# HGD_Sensor_v0_1_-20200729.net
KiCad netlist of a schematic drawn in Altium Designer
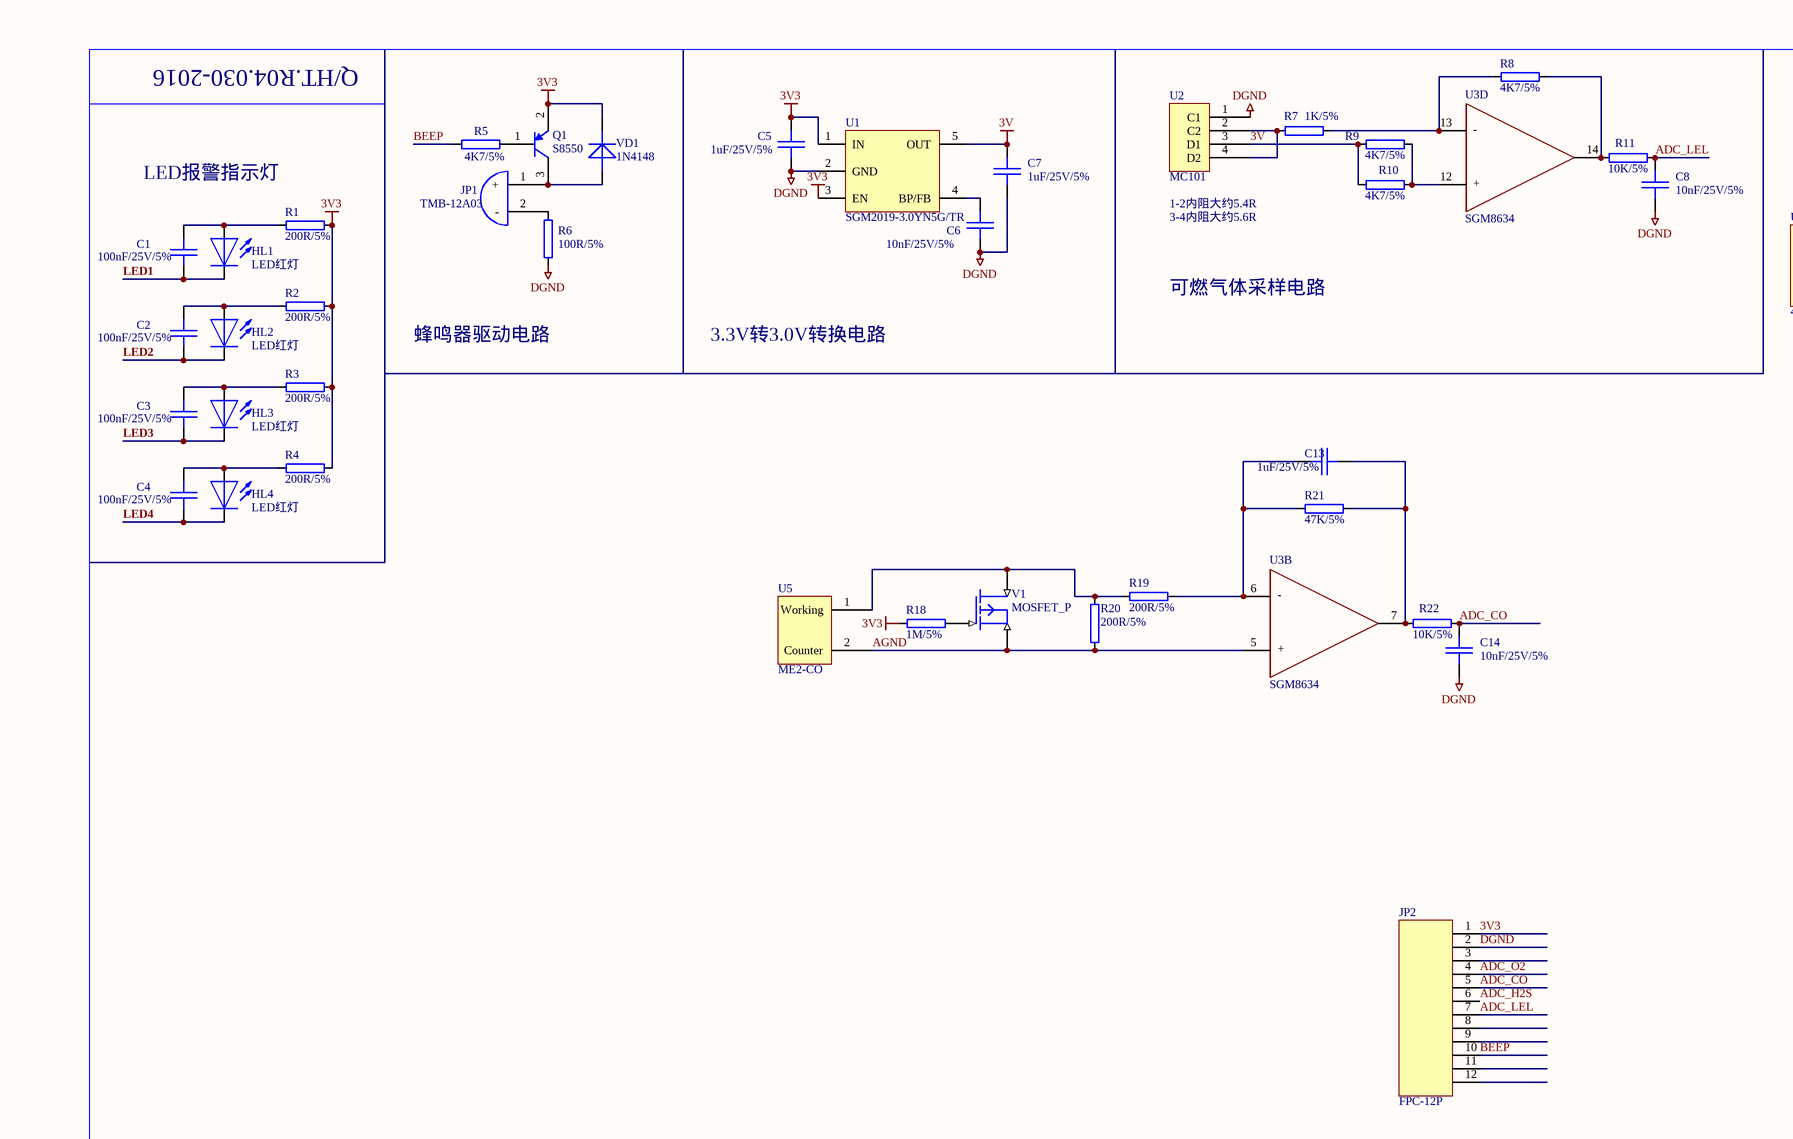
[diagram p0: HGD_Sensor(v0.1)-20200729.SchDoc, top left]
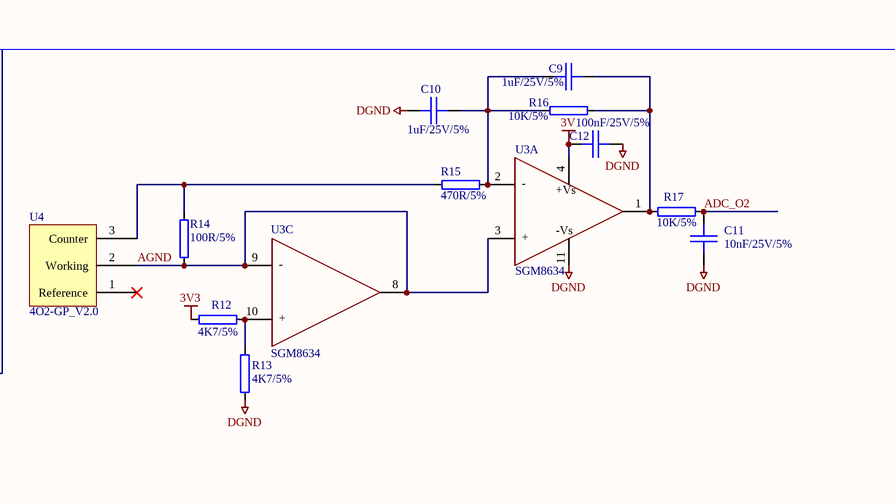
[diagram p1: HGD_Sensor(v0.1)-20200729.SchDoc, top right]
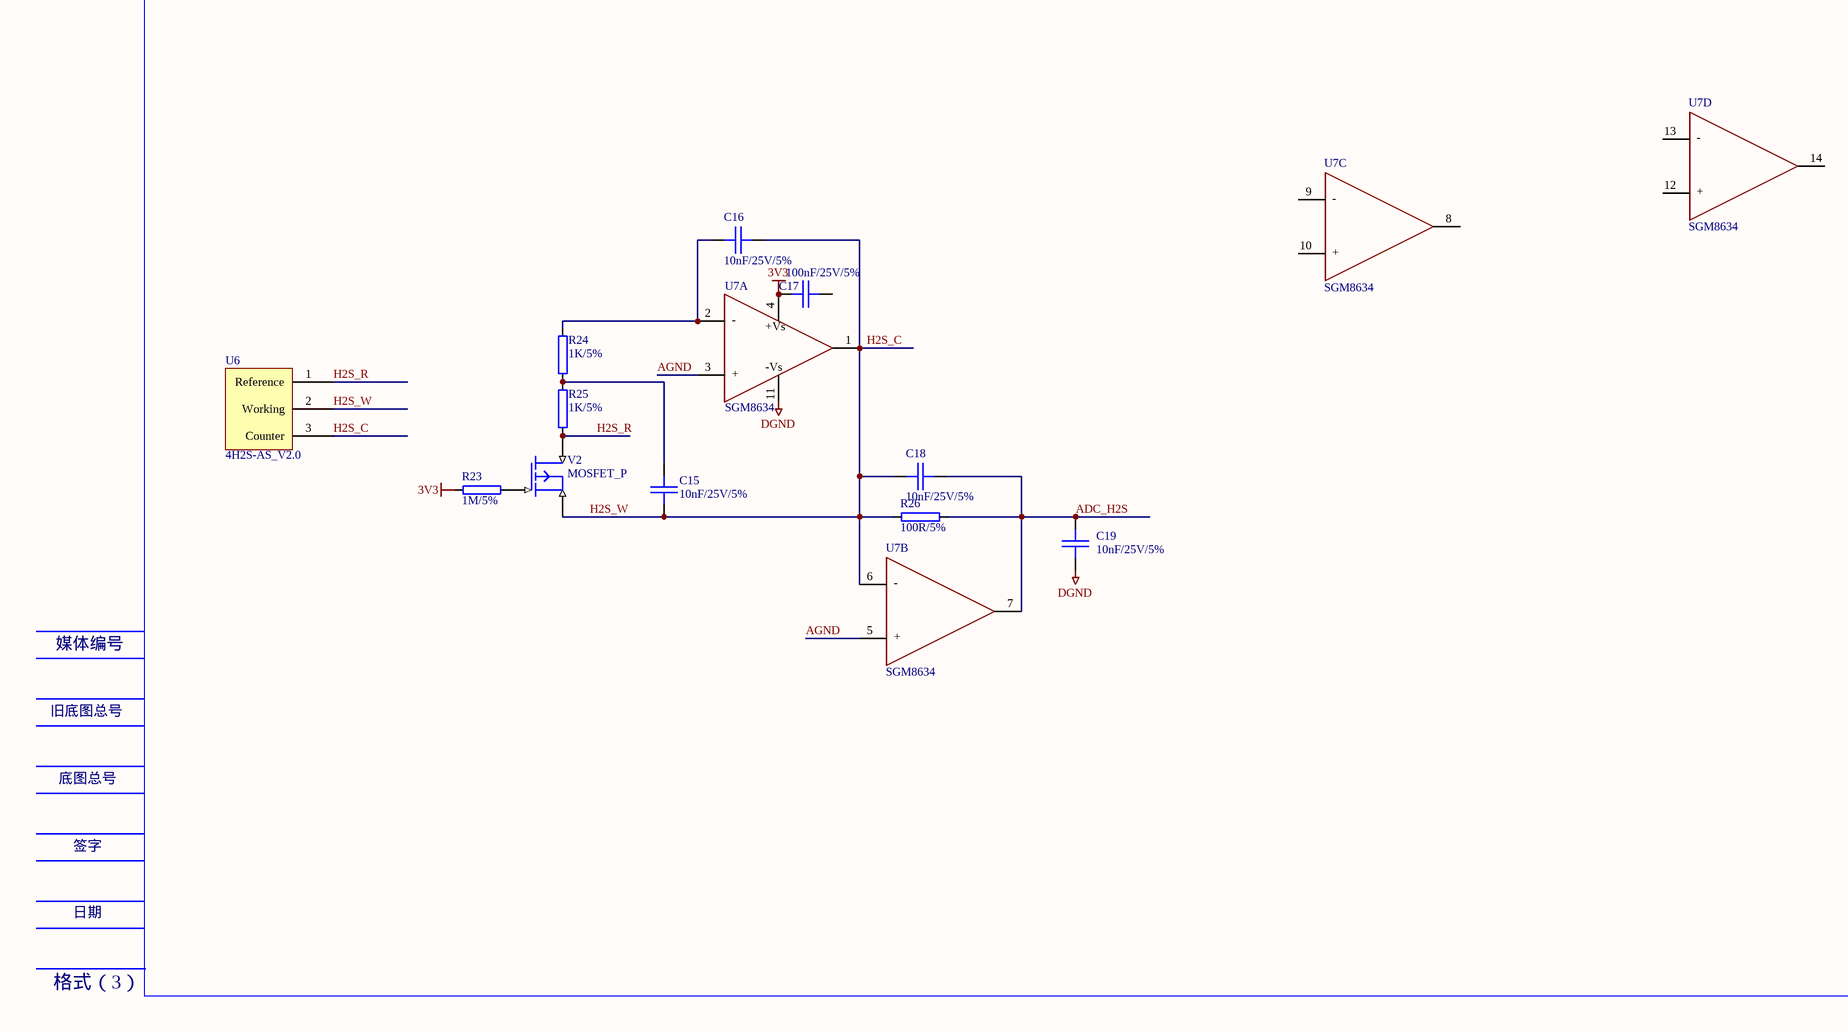
[diagram p2: HGD_Sensor(v0.1)-20200729.SchDoc, bottom left]
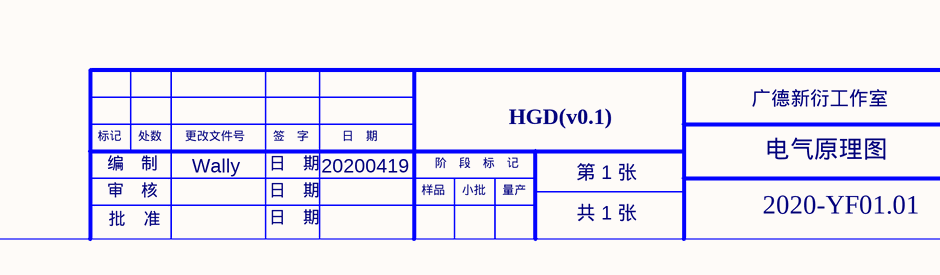
[diagram p3: HGD_Sensor(v0.1)-20200729.SchDoc, bottom right]

(export (version "E")
  (design (tool "Eeschema 10.0.6"))
  (components
    (comp (ref "C1")
      (value "100nF/25V/5%")
      (footprint "C0603")
      (description "电容")
      (libsource (lib "*") (part "CAP"))
    )
    (comp (ref "C2")
      (value "100nF/25V/5%")
      (footprint "C0603")
      (description "电容")
      (libsource (lib "*") (part "CAP"))
    )
    (comp (ref "C3")
      (value "100nF/25V/5%")
      (footprint "C0603")
      (description "电容")
      (libsource (lib "*") (part "CAP"))
    )
    (comp (ref "C4")
      (value "100nF/25V/5%")
      (footprint "C0603")
      (description "电容")
      (libsource (lib "*") (part "CAP"))
    )
    (comp (ref "C5")
      (value "1uF/25V/5%")
      (footprint "0805")
      (description "电容")
      (libsource (lib "*") (part "CAP"))
    )
    (comp (ref "C6")
      (value "10nF/25V/5%")
      (footprint "C0603")
      (description "电容")
      (libsource (lib "*") (part "CAP"))
    )
    (comp (ref "C7")
      (value "1uF/25V/5%")
      (footprint "0805")
      (description "电容")
      (libsource (lib "*") (part "CAP"))
    )
    (comp (ref "C8")
      (value "10nF/25V/5%")
      (footprint "C0603")
      (description "电容")
      (libsource (lib "*") (part "CAP"))
    )
    (comp (ref "C9")
      (value "1uF/25V/5%")
      (footprint "0805")
      (description "电容")
      (libsource (lib "*") (part "CAP"))
    )
    (comp (ref "C10")
      (value "1uF/25V/5%")
      (footprint "C0603")
      (description "电容")
      (libsource (lib "*") (part "CAP"))
    )
    (comp (ref "C11")
      (value "10nF/25V/5%")
      (footprint "C0603")
      (description "电容")
      (libsource (lib "*") (part "CAP"))
    )
    (comp (ref "C12")
      (value "100nF/25V/5%")
      (footprint "C0603")
      (description "电容")
      (libsource (lib "*") (part "CAP"))
    )
    (comp (ref "C13")
      (value "1uF/25V/5%")
      (footprint "0805")
      (description "电容")
      (libsource (lib "*") (part "CAP"))
    )
    (comp (ref "C14")
      (value "10nF/25V/5%")
      (footprint "C0603")
      (description "电容")
      (libsource (lib "*") (part "CAP"))
    )
    (comp (ref "C15")
      (value "10nF/25V/5%")
      (footprint "C0603")
      (description "电容")
      (libsource (lib "*") (part "CAP"))
    )
    (comp (ref "C16")
      (value "10nF/25V/5%")
      (footprint "C0603")
      (description "电容")
      (libsource (lib "*") (part "CAP"))
    )
    (comp (ref "C17")
      (value "100nF/25V/5%")
      (footprint "C0603")
      (description "电容")
      (libsource (lib "*") (part "CAP"))
    )
    (comp (ref "C18")
      (value "10nF/25V/5%")
      (footprint "C0603")
      (description "电容")
      (libsource (lib "*") (part "CAP"))
    )
    (comp (ref "C19")
      (value "10nF/25V/5%")
      (footprint "C0603")
      (description "电容")
      (libsource (lib "*") (part "CAP"))
    )
    (comp (ref "HL1")
      (value "LED红灯")
      (footprint "LED-3MM")
      (description "发光二极管")
      (libsource (lib "wypPCB_Lib") (part "发光二极管"))
    )
    (comp (ref "HL2")
      (value "LED红灯")
      (footprint "LED-3MM")
      (description "发光二极管")
      (libsource (lib "wypPCB_Lib") (part "发光二极管"))
    )
    (comp (ref "HL3")
      (value "LED红灯")
      (footprint "LED-3MM")
      (description "发光二极管")
      (libsource (lib "wypPCB_Lib") (part "发光二极管"))
    )
    (comp (ref "HL4")
      (value "LED红灯")
      (footprint "LED-3MM")
      (description "发光二极管")
      (libsource (lib "wypPCB_Lib") (part "发光二极管"))
    )
    (comp (ref "JP1")
      (value "TMB-12A03")
      (footprint "TMB-12A03")
      (description "TMB-12A03：3.3V有源蜂鸣器")
      (libsource (lib "wypPCB_Lib") (part "TMB-12A03"))
    )
    (comp (ref "JP2")
      (value "FPC-12P")
      (footprint "FPC-1.0MM-12P-W")
      (libsource (lib "wypPCB_Lib") (part "FPC-12P"))
    )
    (comp (ref "Q1")
      (value "S8550")
      (footprint "S8550_SOT-23_95P245X110-3N")
      (description "S8550 PNP型硅三极管")
      (libsource (lib "wypPCB_Lib") (part "S8550"))
    )
    (comp (ref "R1")
      (value "200R/5%")
      (footprint "R0603")
      (description "电阻")
      (libsource (lib "*") (part "RES2"))
    )
    (comp (ref "R2")
      (value "200R/5%")
      (footprint "R0603")
      (description "电阻")
      (libsource (lib "*") (part "RES2"))
    )
    (comp (ref "R3")
      (value "200R/5%")
      (footprint "R0603")
      (description "电阻")
      (libsource (lib "*") (part "RES2"))
    )
    (comp (ref "R4")
      (value "200R/5%")
      (footprint "R0603")
      (description "电阻")
      (libsource (lib "*") (part "RES2"))
    )
    (comp (ref "R5")
      (value "4K7/5%")
      (footprint "R0603")
      (description "电阻")
      (libsource (lib "*") (part "RES2"))
    )
    (comp (ref "R6")
      (value "100R/5%")
      (footprint "R0603")
      (description "电阻")
      (libsource (lib "*") (part "RES2"))
    )
    (comp (ref "R7")
      (value "1K/5%")
      (footprint "R0603")
      (description "电阻")
      (libsource (lib "*") (part "RES2"))
    )
    (comp (ref "R8")
      (value "4K7/5%")
      (footprint "R0603")
      (description "电阻")
      (libsource (lib "*") (part "RES2"))
    )
    (comp (ref "R9")
      (value "4K7/5%")
      (footprint "R0603")
      (description "电阻")
      (libsource (lib "*") (part "RES2"))
    )
    (comp (ref "R10")
      (value "4K7/5%")
      (footprint "R0603")
      (description "电阻")
      (libsource (lib "*") (part "RES2"))
    )
    (comp (ref "R11")
      (value "10K/5%")
      (footprint "R0603")
      (description "电阻")
      (libsource (lib "*") (part "RES2"))
    )
    (comp (ref "R12")
      (value "4K7/5%")
      (footprint "R0603")
      (description "电阻")
      (libsource (lib "*") (part "RES2"))
    )
    (comp (ref "R13")
      (value "4K7/5%")
      (footprint "R0603")
      (description "电阻")
      (libsource (lib "*") (part "RES2"))
    )
    (comp (ref "R14")
      (value "100R/5%")
      (footprint "R0603")
      (description "电阻")
      (libsource (lib "*") (part "RES2"))
    )
    (comp (ref "R15")
      (value "470R/5%")
      (footprint "R0603")
      (description "电阻")
      (libsource (lib "*") (part "RES2"))
    )
    (comp (ref "R16")
      (value "10K/5%")
      (footprint "R0603")
      (description "电阻")
      (libsource (lib "*") (part "RES2"))
    )
    (comp (ref "R17")
      (value "10K/5%")
      (footprint "R0603")
      (description "电阻")
      (libsource (lib "*") (part "RES2"))
    )
    (comp (ref "R18")
      (value "1M/5%")
      (footprint "R0603")
      (description "电阻")
      (libsource (lib "*") (part "RES2"))
    )
    (comp (ref "R19")
      (value "200R/5%")
      (footprint "R0603")
      (description "电阻")
      (libsource (lib "*") (part "RES2"))
    )
    (comp (ref "R20")
      (value "200R/5%")
      (footprint "R0603")
      (description "电阻")
      (libsource (lib "*") (part "RES2"))
    )
    (comp (ref "R21")
      (value "47K/5%")
      (footprint "R0603")
      (description "电阻")
      (libsource (lib "*") (part "RES2"))
    )
    (comp (ref "R22")
      (value "10K/5%")
      (footprint "R0603")
      (description "电阻")
      (libsource (lib "*") (part "RES2"))
    )
    (comp (ref "R23")
      (value "1M/5%")
      (footprint "R0603")
      (description "电阻")
      (libsource (lib "*") (part "RES2"))
    )
    (comp (ref "R24")
      (value "1K/5%")
      (footprint "R0603")
      (description "电阻")
      (libsource (lib "*") (part "RES2"))
    )
    (comp (ref "R25")
      (value "1K/5%")
      (footprint "R0603")
      (description "电阻")
      (libsource (lib "*") (part "RES2"))
    )
    (comp (ref "R26")
      (value "100R/5%")
      (footprint "R0603")
      (description "电阻")
      (libsource (lib "*") (part "RES2"))
    )
    (comp (ref "U1")
      (value "SGM2019-3.0YN5G/TR")
      (footprint "SGM2019_SOT23-5_95P280X125-5N")
      (description "SGM2019：Low Power, Low Dropout, RF Linear Regulators")
      (libsource (lib "wypPCB_Lib") (part "SGM2019"))
    )
    (comp (ref "U2")
      (value "MC101")
      (footprint "MC101")
      (description "MC101：可燃气体传感器")
      (libsource (lib "wypPCB_Lib") (part "MC101"))
    )
    (comp (ref "U3")
      (value "SGM8634")
      (footprint "SGM8634_TSSOP14_65P640X120-14N")
      (description "SGM8634：470μA, 6MHz, Rail-to-Rail I/O, CMOS Operational Amplifier")
      (libsource (lib "wypPCB_Lib") (part "SGM8634"))
    )
    (comp (ref "U4")
      (value "4O2-GP_V2.0")
      (footprint "4O2-GP_V2.0-1.5K-3.2*2.5*5.8")
      (description "4O2-GP_V2.0：O2传感器")
      (libsource (lib "wypPCB_Lib") (part "4O2-GP_V2.0"))
    )
    (comp (ref "U5")
      (value "ME2-CO")
      (footprint "ME2-CO_1.5K-3.2*2.5*5.8")
      (description "ME2-CO：CO传感器")
      (libsource (lib "wypPCB_Lib") (part "ME2-CO"))
    )
    (comp (ref "U6")
      (value "4H2S-AS_V2.0")
      (footprint "4H2S-AS_V2.0-1.5K-3.0*2.5*5.8")
      (description "4H2S-AS_V2.0：H2S传感器")
      (libsource (lib "wypPCB_Lib") (part "4H2S-AS_V2.0"))
    )
    (comp (ref "U7")
      (value "SGM8634")
      (footprint "SGM8634_TSSOP14_65P640X120-14N")
      (description "SGM8634：470μA, 6MHz, Rail-to-Rail I/O, CMOS Operational Amplifier")
      (libsource (lib "wypPCB_Lib") (part "SGM8634"))
    )
    (comp (ref "V1")
      (value "MOSFET_P")
      (footprint "SOT-23-MOS")
      (description "P沟道绝缘栅场效应管_增强型")
      (libsource (lib "ESLIB(v1.1)-AD9-20150731") (part "MOSFET_P"))
    )
    (comp (ref "V2")
      (value "MOSFET_P")
      (footprint "SOT-23-MOS")
      (description "P沟道绝缘栅场效应管_增强型")
      (libsource (lib "ESLIB(v1.1)-AD9-20150731") (part "MOSFET_P"))
    )
    (comp (ref "VD1")
      (value "1N4148")
      (footprint "LL-34")
      (description "开关二极管")
      (libsource (lib "wypPCB_Lib") (part "开关二极管"))
    )
  )
  (nets
    (net (code "1") (name "/ADC_CO") (class "Default")
      (node (ref "C14") (pin "1") (pintype "passive"))
      (node (ref "JP2") (pin "5") (pintype "passive"))
      (node (ref "R22") (pin "1") (pintype "passive"))
    )
    (net (code "2") (name "/ADC_H2S") (class "Default")
      (node (ref "C18") (pin "1") (pintype "passive"))
      (node (ref "C19") (pin "1") (pintype "passive"))
      (node (ref "JP2") (pin "6") (pintype "passive"))
      (node (ref "R26") (pin "2") (pintype "passive"))
      (node (ref "U7") (pin "7") (pintype "passive"))
    )
    (net (code "3") (name "/ADC_LEL") (class "Default")
      (node (ref "C8") (pin "1") (pintype "passive"))
      (node (ref "JP2") (pin "7") (pintype "passive"))
      (node (ref "R11") (pin "1") (pintype "passive"))
    )
    (net (code "4") (name "/ADC_O2") (class "Default")
      (node (ref "C11") (pin "1") (pintype "passive"))
      (node (ref "JP2") (pin "4") (pintype "passive"))
      (node (ref "R17") (pin "1") (pintype "passive"))
    )
    (net (code "5") (name "/AGND") (class "Default")
      (node (ref "R14") (pin "1") (pintype "passive"))
      (node (ref "R20") (pin "2") (pintype "passive"))
      (node (ref "U3") (pin "3") (pinfunction "+_3") (pintype "passive"))
      (node (ref "U3") (pin "5") (pinfunction "+_5") (pintype "passive"))
      (node (ref "U3") (pin "8") (pintype "passive"))
      (node (ref "U3") (pin "9") (pinfunction "-_9") (pintype "passive"))
      (node (ref "U4") (pin "2") (pinfunction "Working_2") (pintype "passive"))
      (node (ref "U5") (pin "2") (pinfunction "Counter_2") (pintype "passive"))
      (node (ref "U7") (pin "3") (pinfunction "+_3") (pintype "passive"))
      (node (ref "U7") (pin "5") (pinfunction "+_5") (pintype "passive"))
      (node (ref "V1") (pin "S") (pinfunction "S_S") (pintype "input"))
    )
    (net (code "6") (name "/BEEP") (class "Default")
      (node (ref "JP2") (pin "10") (pintype "passive"))
      (node (ref "R5") (pin "1") (pintype "passive"))
    )
    (net (code "7") (name "/H2S_C") (class "Default")
      (node (ref "C15") (pin "1") (pintype "passive"))
      (node (ref "C16") (pin "2") (pintype "passive"))
      (node (ref "C18") (pin "2") (pintype "passive"))
      (node (ref "R26") (pin "1") (pintype "passive"))
      (node (ref "U6") (pin "2") (pinfunction "Working_2") (pintype "passive"))
      (node (ref "U6") (pin "3") (pinfunction "Counter_3") (pintype "passive"))
      (node (ref "U7") (pin "1") (pintype "passive"))
      (node (ref "U7") (pin "6") (pinfunction "-_6") (pintype "passive"))
      (node (ref "V2") (pin "S") (pinfunction "S_S") (pintype "input"))
    )
    (net (code "8") (name "/H2S_R") (class "Default")
      (node (ref "R25") (pin "2") (pintype "passive"))
      (node (ref "U6") (pin "1") (pinfunction "Reference_1") (pintype "passive"))
      (node (ref "V2") (pin "D") (pinfunction "D_D") (pintype "input"))
    )
    (net (code "9") (name "/LED1") (class "Default")
      (node (ref "C1") (pin "2") (pintype "passive"))
      (node (ref "HL1") (pin "K") (pintype "passive"))
    )
    (net (code "10") (name "/LED2") (class "Default")
      (node (ref "C2") (pin "2") (pintype "passive"))
      (node (ref "HL2") (pin "K") (pintype "passive"))
    )
    (net (code "11") (name "/LED3") (class "Default")
      (node (ref "C3") (pin "2") (pintype "passive"))
      (node (ref "HL3") (pin "K") (pintype "passive"))
    )
    (net (code "12") (name "/LED4") (class "Default")
      (node (ref "C4") (pin "2") (pintype "passive"))
      (node (ref "HL4") (pin "K") (pintype "passive"))
    )
    (net (code "13") (name "3V") (class "Default")
      (node (ref "C12") (pin "2") (pintype "passive"))
      (node (ref "C7") (pin "1") (pintype "passive"))
      (node (ref "R10") (pin "2") (pintype "passive"))
      (node (ref "R9") (pin "2") (pintype "passive"))
      (node (ref "U1") (pin "5") (pinfunction "OUT_5") (pintype "passive"))
      (node (ref "U2") (pin "3") (pinfunction "D1_3") (pintype "passive"))
      (node (ref "U3") (pin "4") (pinfunction "+Vs_4") (pintype "passive"))
    )
    (net (code "14") (name "3V3") (class "Default")
      (node (ref "C17") (pin "2") (pintype "passive"))
      (node (ref "C5") (pin "1") (pintype "passive"))
      (node (ref "JP2") (pin "1") (pintype "passive"))
      (node (ref "Q1") (pin "2") (pinfunction "E_2") (pintype "passive"))
      (node (ref "R1") (pin "2") (pintype "passive"))
      (node (ref "R12") (pin "2") (pintype "passive"))
      (node (ref "R18") (pin "2") (pintype "passive"))
      (node (ref "R2") (pin "2") (pintype "passive"))
      (node (ref "R23") (pin "2") (pintype "passive"))
      (node (ref "R3") (pin "2") (pintype "passive"))
      (node (ref "R4") (pin "2") (pintype "passive"))
      (node (ref "U1") (pin "1") (pinfunction "IN_1") (pintype "passive"))
      (node (ref "U1") (pin "3") (pinfunction "EN_3") (pintype "passive"))
      (node (ref "U7") (pin "4") (pinfunction "+Vs_4") (pintype "passive"))
      (node (ref "VD1") (pin "K") (pintype "passive"))
    )
    (net (code "15") (name "DGND") (class "Default")
      (node (ref "C10") (pin "2") (pintype "passive"))
      (node (ref "C11") (pin "2") (pintype "passive"))
      (node (ref "C12") (pin "1") (pintype "passive"))
      (node (ref "C14") (pin "2") (pintype "passive"))
      (node (ref "C19") (pin "2") (pintype "passive"))
      (node (ref "C5") (pin "2") (pintype "passive"))
      (node (ref "C6") (pin "2") (pintype "passive"))
      (node (ref "C7") (pin "2") (pintype "passive"))
      (node (ref "C8") (pin "2") (pintype "passive"))
      (node (ref "JP2") (pin "2") (pintype "passive"))
      (node (ref "R13") (pin "2") (pintype "passive"))
      (node (ref "R6") (pin "1") (pintype "passive"))
      (node (ref "U1") (pin "2") (pinfunction "GND_2") (pintype "passive"))
      (node (ref "U2") (pin "1") (pinfunction "C1_1") (pintype "passive"))
      (node (ref "U3") (pin "11") (pinfunction "-Vs_11") (pintype "passive"))
      (node (ref "U7") (pin "11") (pinfunction "-Vs_11") (pintype "passive"))
    )
    (net (code "16") (name "Net-(C1-Pad1)") (class "Default")
      (node (ref "C1") (pin "1") (pintype "passive"))
      (node (ref "HL1") (pin "A") (pintype "passive"))
      (node (ref "R1") (pin "1") (pintype "passive"))
    )
    (net (code "17") (name "Net-(C2-Pad1)") (class "Default")
      (node (ref "C2") (pin "1") (pintype "passive"))
      (node (ref "HL2") (pin "A") (pintype "passive"))
      (node (ref "R2") (pin "1") (pintype "passive"))
    )
    (net (code "18") (name "Net-(C3-Pad1)") (class "Default")
      (node (ref "C3") (pin "1") (pintype "passive"))
      (node (ref "HL3") (pin "A") (pintype "passive"))
      (node (ref "R3") (pin "1") (pintype "passive"))
    )
    (net (code "19") (name "Net-(C4-Pad1)") (class "Default")
      (node (ref "C4") (pin "1") (pintype "passive"))
      (node (ref "HL4") (pin "A") (pintype "passive"))
      (node (ref "R4") (pin "1") (pintype "passive"))
    )
    (net (code "20") (name "Net-(C9-Pad2)") (class "Default")
      (node (ref "C9") (pin "2") (pintype "passive"))
      (node (ref "R16") (pin "1") (pintype "passive"))
      (node (ref "R17") (pin "2") (pintype "passive"))
      (node (ref "U3") (pin "1") (pintype "passive"))
    )
    (net (code "21") (name "Net-(C13-Pad2)") (class "Default")
      (node (ref "C13") (pin "2") (pintype "passive"))
      (node (ref "R21") (pin "2") (pintype "passive"))
      (node (ref "R22") (pin "2") (pintype "passive"))
      (node (ref "U3") (pin "7") (pintype "passive"))
    )
    (net (code "22") (name "Net-(C15-Pad2)") (class "Default")
      (node (ref "C15") (pin "2") (pintype "passive"))
      (node (ref "R24") (pin "2") (pintype "passive"))
      (node (ref "R25") (pin "1") (pintype "passive"))
    )
    (net (code "23") (name "Net-(JP1-+)") (class "Default")
      (node (ref "JP1") (pin "1") (pinfunction "+_1") (pintype "passive"))
      (node (ref "Q1") (pin "3") (pinfunction "C_3") (pintype "passive"))
      (node (ref "VD1") (pin "A") (pintype "passive"))
    )
    (net (code "24") (name "Net-(JP1--)") (class "Default")
      (node (ref "JP1") (pin "2") (pinfunction "-_2") (pintype "passive"))
      (node (ref "R6") (pin "2") (pintype "passive"))
    )
    (net (code "25") (name "Net-(Q1-B)") (class "Default")
      (node (ref "Q1") (pin "1") (pinfunction "B_1") (pintype "passive"))
      (node (ref "R5") (pin "2") (pintype "passive"))
    )
    (net (code "26") (name "Net-(R11-Pad2)") (class "Default")
      (node (ref "R11") (pin "2") (pintype "passive"))
      (node (ref "R8") (pin "1") (pintype "passive"))
      (node (ref "U3") (pin "14") (pintype "passive"))
    )
    (net (code "27") (name "Net-(R18-Pad1)") (class "Default")
      (node (ref "R18") (pin "1") (pintype "passive"))
      (node (ref "V1") (pin "G") (pinfunction "G_G") (pintype "input"))
    )
    (net (code "28") (name "Net-(R23-Pad1)") (class "Default")
      (node (ref "R23") (pin "1") (pintype "passive"))
      (node (ref "V2") (pin "G") (pinfunction "G_G") (pintype "input"))
    )
    (net (code "29") (name "Net-(U1-BP{slash}FB)") (class "Default")
      (node (ref "C6") (pin "1") (pintype "passive"))
      (node (ref "U1") (pin "4") (pinfunction "BP/FB_4") (pintype "passive"))
    )
    (net (code "30") (name "Net-(U2-C2)") (class "Default")
      (node (ref "R7") (pin "2") (pintype "passive"))
      (node (ref "U2") (pin "2") (pinfunction "C2_2") (pintype "passive"))
      (node (ref "U2") (pin "4") (pinfunction "D2_4") (pintype "passive"))
    )
    (net (code "31") (name "Net-(U3A--)") (class "Default")
      (node (ref "C10") (pin "1") (pintype "passive"))
      (node (ref "C9") (pin "1") (pintype "passive"))
      (node (ref "R15") (pin "2") (pintype "passive"))
      (node (ref "R16") (pin "2") (pintype "passive"))
      (node (ref "U3") (pin "2") (pinfunction "-_2") (pintype "passive"))
    )
    (net (code "32") (name "Net-(U3B--)") (class "Default")
      (node (ref "C13") (pin "1") (pintype "passive"))
      (node (ref "R19") (pin "1") (pintype "passive"))
      (node (ref "R21") (pin "1") (pintype "passive"))
      (node (ref "U3") (pin "6") (pinfunction "-_6") (pintype "passive"))
    )
    (net (code "33") (name "Net-(U3C-+)") (class "Default")
      (node (ref "R12") (pin "1") (pintype "passive"))
      (node (ref "R13") (pin "1") (pintype "passive"))
      (node (ref "U3") (pin "10") (pinfunction "+_10") (pintype "passive"))
    )
    (net (code "34") (name "Net-(U3D-+)") (class "Default")
      (node (ref "R10") (pin "1") (pintype "passive"))
      (node (ref "R9") (pin "1") (pintype "passive"))
      (node (ref "U3") (pin "12") (pinfunction "+_12") (pintype "passive"))
    )
    (net (code "35") (name "Net-(U3D--)") (class "Default")
      (node (ref "R7") (pin "1") (pintype "passive"))
      (node (ref "R8") (pin "2") (pintype "passive"))
      (node (ref "U3") (pin "13") (pinfunction "-_13") (pintype "passive"))
    )
    (net (code "36") (name "Net-(U4-Counter)") (class "Default")
      (node (ref "R14") (pin "2") (pintype "passive"))
      (node (ref "R15") (pin "1") (pintype "passive"))
      (node (ref "U4") (pin "3") (pinfunction "Counter_3") (pintype "passive"))
    )
    (net (code "37") (name "Net-(U5-Working)") (class "Default")
      (node (ref "R19") (pin "2") (pintype "passive"))
      (node (ref "R20") (pin "1") (pintype "passive"))
      (node (ref "U5") (pin "1") (pinfunction "Working_1") (pintype "passive"))
      (node (ref "V1") (pin "D") (pinfunction "D_D") (pintype "input"))
    )
    (net (code "38") (name "Net-(U7A--)") (class "Default")
      (node (ref "C16") (pin "1") (pintype "passive"))
      (node (ref "R24") (pin "1") (pintype "passive"))
      (node (ref "U7") (pin "2") (pinfunction "-_2") (pintype "passive"))
    )
    (net (code "39") (name "unconnected-(C17-Pad1)") (class "Default")
      (node (ref "C17") (pin "1") (pintype "passive"))
    )
    (net (code "40") (name "unconnected-(JP2-Pad3)") (class "Default")
      (node (ref "JP2") (pin "3") (pintype "passive"))
    )
    (net (code "41") (name "unconnected-(JP2-Pad8)") (class "Default")
      (node (ref "JP2") (pin "8") (pintype "passive"))
    )
    (net (code "42") (name "unconnected-(JP2-Pad9)") (class "Default")
      (node (ref "JP2") (pin "9") (pintype "passive"))
    )
    (net (code "43") (name "unconnected-(JP2-Pad11)") (class "Default")
      (node (ref "JP2") (pin "11") (pintype "passive"))
    )
    (net (code "44") (name "unconnected-(JP2-Pad12)") (class "Default")
      (node (ref "JP2") (pin "12") (pintype "passive"))
    )
    (net (code "45") (name "unconnected-(U4-Reference-Pad1)") (class "Default")
      (node (ref "U4") (pin "1") (pinfunction "Reference_1") (pintype "passive+no_connect"))
    )
    (net (code "46") (name "unconnected-(U7-Pad8)") (class "Default")
      (node (ref "U7") (pin "8") (pintype "passive"))
    )
    (net (code "47") (name "unconnected-(U7-Pad14)") (class "Default")
      (node (ref "U7") (pin "14") (pintype "passive"))
    )
    (net (code "48") (name "unconnected-(U7C-+-Pad10)") (class "Default")
      (node (ref "U7") (pin "10") (pinfunction "+_10") (pintype "passive"))
    )
    (net (code "49") (name "unconnected-(U7C---Pad9)") (class "Default")
      (node (ref "U7") (pin "9") (pinfunction "-_9") (pintype "passive"))
    )
    (net (code "50") (name "unconnected-(U7D-+-Pad12)") (class "Default")
      (node (ref "U7") (pin "12") (pinfunction "+_12") (pintype "passive"))
    )
    (net (code "51") (name "unconnected-(U7D---Pad13)") (class "Default")
      (node (ref "U7") (pin "13") (pinfunction "-_13") (pintype "passive"))
    )
  )
)
